# ADS_ExG.net
KiCad netlist of a schematic drawn in Altium Designer
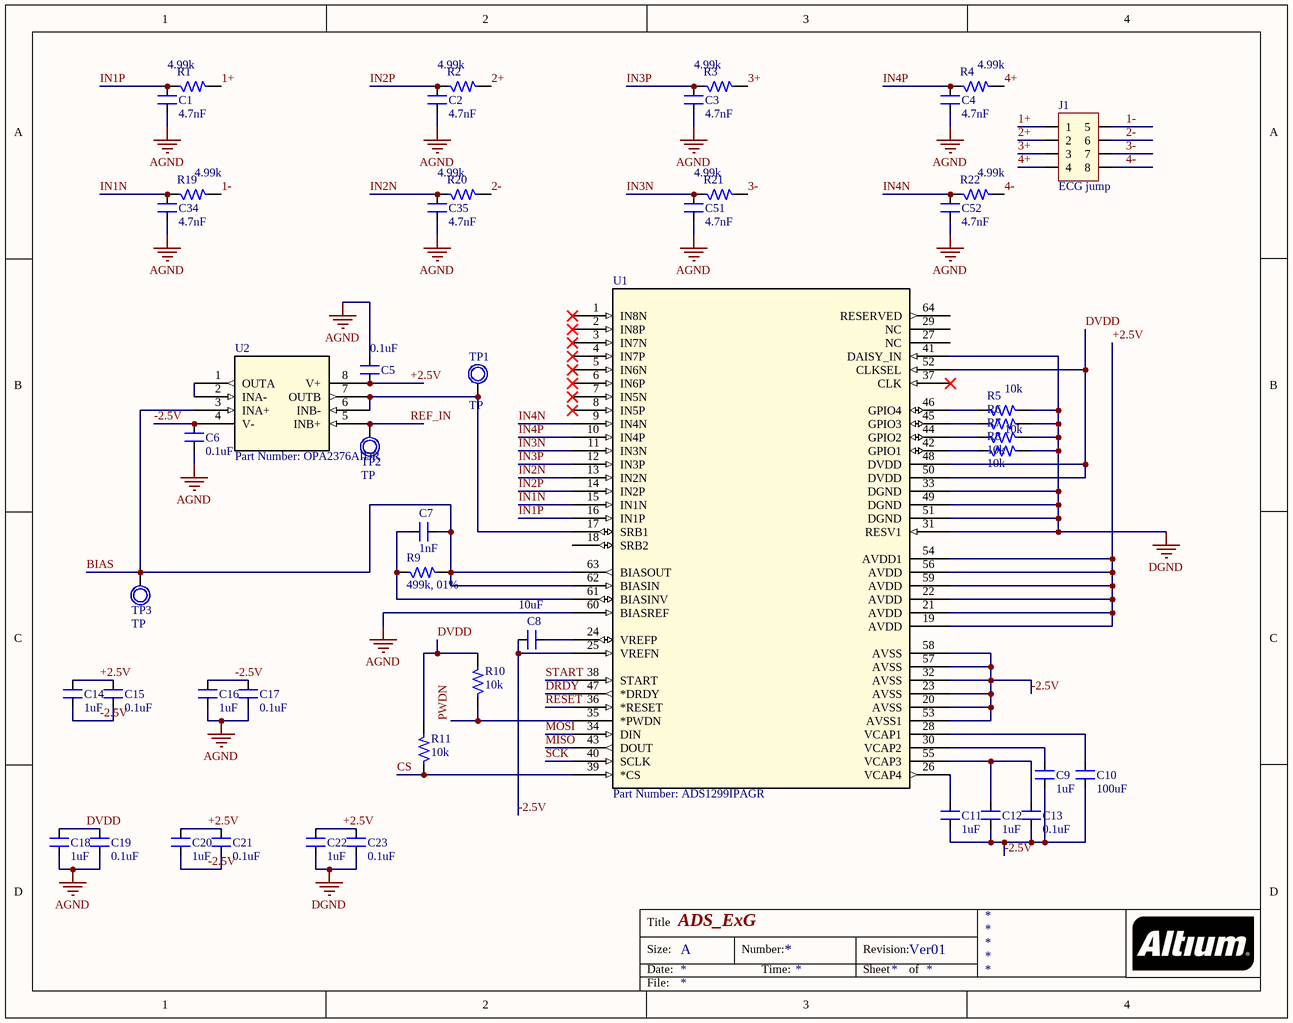
[diagram p0: ADS_ExG.SchDoc]

(export (version "E")
  (design (tool "Eeschema 10.0.6"))
  (components
    (comp (ref "C1")
      (value "4.7nF")
      (footprint "SM-0805")
      (description "Cap SMD")
      (libsource (lib "VioletofSun") (part "CM"))
    )
    (comp (ref "C2")
      (value "4.7nF")
      (footprint "SM-0805")
      (description "Cap SMD")
      (libsource (lib "VioletofSun") (part "CM"))
    )
    (comp (ref "C3")
      (value "4.7nF")
      (footprint "SM-0805")
      (description "Cap SMD")
      (libsource (lib "VioletofSun") (part "CM"))
    )
    (comp (ref "C4")
      (value "4.7nF")
      (footprint "SM-0805")
      (description "Cap SMD")
      (libsource (lib "VioletofSun") (part "CM"))
    )
    (comp (ref "C5")
      (value "0.1uF")
      (footprint "SM-0805")
      (description "Cap SMD")
      (libsource (lib "VioletofSun") (part "CM"))
    )
    (comp (ref "C6")
      (value "0.1uF")
      (footprint "SM-0805")
      (description "Cap SMD")
      (libsource (lib "VioletofSun") (part "CM"))
    )
    (comp (ref "C7")
      (value "1nF")
      (footprint "SM-0805")
      (description "Cap SMD")
      (libsource (lib "VioletofSun") (part "CM"))
    )
    (comp (ref "C8")
      (value "10uF")
      (footprint "SM-0805")
      (description "Cap SMD")
      (libsource (lib "VioletofSun") (part "CM"))
    )
    (comp (ref "C9")
      (value "1uF")
      (footprint "SM-0805")
      (description "Cap SMD")
      (libsource (lib "VioletofSun") (part "CM"))
    )
    (comp (ref "C10")
      (value "100uF")
      (footprint "SM-0805")
      (description "Cap SMD")
      (libsource (lib "VioletofSun") (part "CM"))
    )
    (comp (ref "C11")
      (value "1uF")
      (footprint "SM-0805")
      (description "Cap SMD")
      (libsource (lib "VioletofSun") (part "CM"))
    )
    (comp (ref "C12")
      (value "1uF")
      (footprint "SM-0805")
      (description "Cap SMD")
      (libsource (lib "VioletofSun") (part "CM"))
    )
    (comp (ref "C13")
      (value "0.1uF")
      (footprint "SM-0805")
      (description "Cap SMD")
      (libsource (lib "VioletofSun") (part "CM"))
    )
    (comp (ref "C14")
      (value "1uF")
      (footprint "SM-0805")
      (description "Cap SMD")
      (libsource (lib "VioletofSun") (part "CM"))
    )
    (comp (ref "C15")
      (value "0.1uF")
      (footprint "SM-0805")
      (description "Cap SMD")
      (libsource (lib "VioletofSun") (part "CM"))
    )
    (comp (ref "C16")
      (value "1uF")
      (footprint "SM-0805")
      (description "Cap SMD")
      (libsource (lib "VioletofSun") (part "CM"))
    )
    (comp (ref "C17")
      (value "0.1uF")
      (footprint "SM-0805")
      (description "Cap SMD")
      (libsource (lib "VioletofSun") (part "CM"))
    )
    (comp (ref "C18")
      (value "1uF")
      (footprint "SM-0805")
      (description "Cap SMD")
      (libsource (lib "VioletofSun") (part "CM"))
    )
    (comp (ref "C19")
      (value "0.1uF")
      (footprint "SM-0805")
      (description "Cap SMD")
      (libsource (lib "VioletofSun") (part "CM"))
    )
    (comp (ref "C20")
      (value "1uF")
      (footprint "SM-0805")
      (description "Cap SMD")
      (libsource (lib "VioletofSun") (part "CM"))
    )
    (comp (ref "C21")
      (value "0.1uF")
      (footprint "SM-0805")
      (description "Cap SMD")
      (libsource (lib "VioletofSun") (part "CM"))
    )
    (comp (ref "C22")
      (value "1uF")
      (footprint "SM-0805")
      (description "Cap SMD")
      (libsource (lib "VioletofSun") (part "CM"))
    )
    (comp (ref "C23")
      (value "0.1uF")
      (footprint "SM-0805")
      (description "Cap SMD")
      (libsource (lib "VioletofSun") (part "CM"))
    )
    (comp (ref "C34")
      (value "4.7nF")
      (footprint "SM-0805")
      (description "Cap SMD")
      (libsource (lib "VioletofSun") (part "CM"))
    )
    (comp (ref "C35")
      (value "4.7nF")
      (footprint "SM-0805")
      (description "Cap SMD")
      (libsource (lib "VioletofSun") (part "CM"))
    )
    (comp (ref "C51")
      (value "4.7nF")
      (footprint "SM-0805")
      (description "Cap SMD")
      (libsource (lib "VioletofSun") (part "CM"))
    )
    (comp (ref "C52")
      (value "4.7nF")
      (footprint "SM-0805")
      (description "Cap SMD")
      (libsource (lib "VioletofSun") (part "CM"))
    )
    (comp (ref "J1")
      (value "ECG jump")
      (footprint "JP4x2")
      (description "Connector 4x2")
      (libsource (lib "VioletofSun") (part "JP4x2"))
    )
    (comp (ref "R1")
      (value "4.99k")
      (footprint "SM-0805")
      (description "Resistor 1/4W")
      (libsource (lib "VioletofSun") (part "R"))
    )
    (comp (ref "R2")
      (value "4.99k")
      (footprint "SM-0805")
      (description "Resistor 1/4W")
      (libsource (lib "VioletofSun") (part "R"))
    )
    (comp (ref "R3")
      (value "4.99k")
      (footprint "SM-0805")
      (description "Resistor 1/4W")
      (libsource (lib "VioletofSun") (part "R"))
    )
    (comp (ref "R4")
      (value "4.99k")
      (footprint "SM-0805")
      (description "Resistor 1/4W")
      (libsource (lib "VioletofSun") (part "R"))
    )
    (comp (ref "R5")
      (value "10k")
      (footprint "SM-0805")
      (description "Resistor 1/4W")
      (libsource (lib "VioletofSun") (part "R"))
    )
    (comp (ref "R6")
      (value "10k")
      (footprint "SM-0805")
      (description "Resistor 1/4W")
      (libsource (lib "VioletofSun") (part "R"))
    )
    (comp (ref "R7")
      (value "10k")
      (footprint "SM-0805")
      (description "Resistor 1/4W")
      (libsource (lib "VioletofSun") (part "R"))
    )
    (comp (ref "R8")
      (value "10k")
      (footprint "SM-0805")
      (description "Resistor 1/4W")
      (libsource (lib "VioletofSun") (part "R"))
    )
    (comp (ref "R9")
      (value "499k, 01%")
      (footprint "SM-0805")
      (description "Resistor 1/4W")
      (libsource (lib "VioletofSun") (part "R"))
    )
    (comp (ref "R10")
      (value "10k")
      (footprint "SM-0805")
      (description "Resistor 1/4W")
      (libsource (lib "VioletofSun") (part "R"))
    )
    (comp (ref "R11")
      (value "10k")
      (footprint "SM-0805")
      (description "Resistor 1/4W")
      (libsource (lib "VioletofSun") (part "R"))
    )
    (comp (ref "R19")
      (value "4.99k")
      (footprint "SM-0805")
      (description "Resistor 1/4W")
      (libsource (lib "VioletofSun") (part "R"))
    )
    (comp (ref "R20")
      (value "4.99k")
      (footprint "SM-0805")
      (description "Resistor 1/4W")
      (libsource (lib "VioletofSun") (part "R"))
    )
    (comp (ref "R21")
      (value "4.99k")
      (footprint "SM-0805")
      (description "Resistor 1/4W")
      (libsource (lib "VioletofSun") (part "R"))
    )
    (comp (ref "R22")
      (value "4.99k")
      (footprint "SM-0805")
      (description "Resistor 1/4W")
      (libsource (lib "VioletofSun") (part "R"))
    )
    (comp (ref "TP1")
      (value "TP")
      (footprint "VioletofSun:TP1")
      (description "Test Point")
      (libsource (lib "") (part "TP1_1"))
    )
    (comp (ref "TP2")
      (value "TP")
      (footprint "VioletofSun:TP1")
      (description "Test Point")
      (libsource (lib "VioletofSun") (part "TP1"))
    )
    (comp (ref "TP3")
      (value "TP")
      (footprint "VioletofSun:TP1")
      (description "Test Point")
      (libsource (lib "VioletofSun") (part "TP1"))
    )
    (comp (ref "U1")
      (value "Part Number: ADS1299IPAGR")
      (footprint "PAG64")
      (description "No Description Available")
      (fields
        (field (name "MANUFACTURER_PART_NUMBER") "ADS1299IPAGR")
        (field (name "COPYRIGHT") "Copyright (C) 2018 Accelerated Designs. All rights reserved")
      )
      (libsource (lib "ADS1299IPAGR") (part "ADS1299IPAGR"))
    )
    (comp (ref "U2")
      (value "Part Number: OPA2376AIDR")
      (footprint "D8")
      (description "No Description Available")
      (fields
        (field (name "MANUFACTURER_PART_NUMBER") "OPA2376AIDR")
        (field (name "COPYRIGHT") "Copyright (C) 2018 Accelerated Designs. All rights reserved")
      )
      (libsource (lib "2019-06-26_00-32-27") (part "OPA2376AIDR"))
    )
  )
  (nets
    (net (code "1") (name "/+2.5V") (class "Default")
      (node (ref "C14") (pin "2") (pinfunction "2_2") (pintype "passive"))
      (node (ref "C15") (pin "2") (pinfunction "2_2") (pintype "passive"))
      (node (ref "C20") (pin "2") (pinfunction "2_2") (pintype "passive"))
      (node (ref "C21") (pin "2") (pinfunction "2_2") (pintype "passive"))
      (node (ref "C22") (pin "2") (pinfunction "2_2") (pintype "passive"))
      (node (ref "C23") (pin "2") (pinfunction "2_2") (pintype "passive"))
      (node (ref "C5") (pin "1") (pinfunction "1_1") (pintype "passive"))
      (node (ref "U1") (pin "19") (pinfunction "AVDD_19") (pintype "power_in"))
      (node (ref "U1") (pin "21") (pinfunction "AVDD_21") (pintype "power_in"))
      (node (ref "U1") (pin "22") (pinfunction "AVDD_22") (pintype "power_in"))
      (node (ref "U1") (pin "54") (pinfunction "AVDD1_54") (pintype "power_in"))
      (node (ref "U1") (pin "56") (pinfunction "AVDD_56") (pintype "power_in"))
      (node (ref "U1") (pin "59") (pinfunction "AVDD_59") (pintype "power_in"))
      (node (ref "U2") (pin "8") (pinfunction "V+_8") (pintype "power_in"))
    )
    (net (code "2") (name "/-2.5V") (class "Default")
      (node (ref "C10") (pin "2") (pinfunction "2_2") (pintype "passive"))
      (node (ref "C11") (pin "1") (pinfunction "1_1") (pintype "passive"))
      (node (ref "C12") (pin "1") (pinfunction "1_1") (pintype "passive"))
      (node (ref "C13") (pin "1") (pinfunction "1_1") (pintype "passive"))
      (node (ref "C14") (pin "1") (pinfunction "1_1") (pintype "passive"))
      (node (ref "C15") (pin "1") (pinfunction "1_1") (pintype "passive"))
      (node (ref "C16") (pin "2") (pinfunction "2_2") (pintype "passive"))
      (node (ref "C17") (pin "2") (pinfunction "2_2") (pintype "passive"))
      (node (ref "C20") (pin "1") (pinfunction "1_1") (pintype "passive"))
      (node (ref "C21") (pin "1") (pinfunction "1_1") (pintype "passive"))
      (node (ref "C6") (pin "2") (pinfunction "2_2") (pintype "passive"))
      (node (ref "C8") (pin "2") (pinfunction "2_2") (pintype "passive"))
      (node (ref "C9") (pin "1") (pinfunction "1_1") (pintype "passive"))
      (node (ref "U1") (pin "20") (pinfunction "AVSS_20") (pintype "power_in"))
      (node (ref "U1") (pin "23") (pinfunction "AVSS_23") (pintype "power_in"))
      (node (ref "U1") (pin "25") (pinfunction "VREFN_25") (pintype "input"))
      (node (ref "U1") (pin "32") (pinfunction "AVSS_32") (pintype "power_in"))
      (node (ref "U1") (pin "53") (pinfunction "AVSS1_53") (pintype "power_in"))
      (node (ref "U1") (pin "57") (pinfunction "AVSS_57") (pintype "power_in"))
      (node (ref "U1") (pin "58") (pinfunction "AVSS_58") (pintype "power_in"))
      (node (ref "U2") (pin "4") (pinfunction "V-_4") (pintype "power_in"))
    )
    (net (code "3") (name "/1+") (class "Default")
      (node (ref "J1") (pin "1") (pinfunction "1_1") (pintype "passive"))
      (node (ref "R1") (pin "2") (pinfunction "2_2") (pintype "passive"))
    )
    (net (code "4") (name "/1-") (class "Default")
      (node (ref "J1") (pin "5") (pinfunction "5_5") (pintype "passive"))
      (node (ref "R19") (pin "2") (pinfunction "2_2") (pintype "passive"))
    )
    (net (code "5") (name "/2+") (class "Default")
      (node (ref "J1") (pin "2") (pinfunction "2_2") (pintype "passive"))
      (node (ref "R2") (pin "2") (pinfunction "2_2") (pintype "passive"))
    )
    (net (code "6") (name "/2-") (class "Default")
      (node (ref "J1") (pin "6") (pinfunction "6_6") (pintype "passive"))
      (node (ref "R20") (pin "2") (pinfunction "2_2") (pintype "passive"))
    )
    (net (code "7") (name "/3+") (class "Default")
      (node (ref "J1") (pin "3") (pinfunction "3_3") (pintype "passive"))
      (node (ref "R3") (pin "2") (pinfunction "2_2") (pintype "passive"))
    )
    (net (code "8") (name "/3-") (class "Default")
      (node (ref "J1") (pin "7") (pinfunction "7_7") (pintype "passive"))
      (node (ref "R21") (pin "2") (pinfunction "2_2") (pintype "passive"))
    )
    (net (code "9") (name "/4+") (class "Default")
      (node (ref "J1") (pin "4") (pinfunction "4_4") (pintype "passive"))
      (node (ref "R4") (pin "2") (pinfunction "2_2") (pintype "passive"))
    )
    (net (code "10") (name "/4-") (class "Default")
      (node (ref "J1") (pin "8") (pinfunction "8_8") (pintype "passive"))
      (node (ref "R22") (pin "2") (pinfunction "2_2") (pintype "passive"))
    )
    (net (code "11") (name "/BIAS") (class "Default")
      (node (ref "C7") (pin "2") (pinfunction "2_2") (pintype "passive"))
      (node (ref "R9") (pin "2") (pinfunction "2_2") (pintype "passive"))
      (node (ref "TP3") (pin "1") (pinfunction "1_1") (pintype "passive"))
      (node (ref "U1") (pin "62") (pinfunction "BIASIN_62") (pintype "input"))
      (node (ref "U1") (pin "63") (pinfunction "BIASOUT_63") (pintype "output"))
      (node (ref "U2") (pin "3") (pinfunction "INA+_3") (pintype "input"))
    )
    (net (code "12") (name "/CS") (class "Default")
      (node (ref "R11") (pin "1") (pinfunction "1_1") (pintype "passive"))
      (node (ref "U1") (pin "39") (pinfunction "*CS_39") (pintype "input"))
    )
    (net (code "13") (name "/DRDY") (class "Default")
      (node (ref "U1") (pin "47") (pinfunction "*DRDY_47") (pintype "output"))
    )
    (net (code "14") (name "/DVDD") (class "Default")
      (node (ref "C18") (pin "2") (pinfunction "2_2") (pintype "passive"))
      (node (ref "C19") (pin "2") (pinfunction "2_2") (pintype "passive"))
      (node (ref "R10") (pin "2") (pinfunction "2_2") (pintype "passive"))
      (node (ref "R11") (pin "2") (pinfunction "2_2") (pintype "passive"))
      (node (ref "U1") (pin "48") (pinfunction "DVDD_48") (pintype "power_in"))
      (node (ref "U1") (pin "50") (pinfunction "DVDD_50") (pintype "power_in"))
      (node (ref "U1") (pin "52") (pinfunction "CLKSEL_52") (pintype "input"))
    )
    (net (code "15") (name "/IN1N") (class "Default")
      (node (ref "C34") (pin "2") (pinfunction "2_2") (pintype "passive"))
      (node (ref "R19") (pin "1") (pinfunction "1_1") (pintype "passive"))
      (node (ref "U1") (pin "15") (pinfunction "IN1N_15") (pintype "input"))
    )
    (net (code "16") (name "/IN1P") (class "Default")
      (node (ref "C1") (pin "2") (pinfunction "2_2") (pintype "passive"))
      (node (ref "R1") (pin "1") (pinfunction "1_1") (pintype "passive"))
      (node (ref "U1") (pin "16") (pinfunction "IN1P_16") (pintype "input"))
    )
    (net (code "17") (name "/IN2N") (class "Default")
      (node (ref "C35") (pin "2") (pinfunction "2_2") (pintype "passive"))
      (node (ref "R20") (pin "1") (pinfunction "1_1") (pintype "passive"))
      (node (ref "U1") (pin "13") (pinfunction "IN2N_13") (pintype "input"))
    )
    (net (code "18") (name "/IN2P") (class "Default")
      (node (ref "C2") (pin "2") (pinfunction "2_2") (pintype "passive"))
      (node (ref "R2") (pin "1") (pinfunction "1_1") (pintype "passive"))
      (node (ref "U1") (pin "14") (pinfunction "IN2P_14") (pintype "input"))
    )
    (net (code "19") (name "/IN3N") (class "Default")
      (node (ref "C51") (pin "2") (pinfunction "2_2") (pintype "passive"))
      (node (ref "R21") (pin "1") (pinfunction "1_1") (pintype "passive"))
      (node (ref "U1") (pin "11") (pinfunction "IN3N_11") (pintype "input"))
    )
    (net (code "20") (name "/IN3P") (class "Default")
      (node (ref "C3") (pin "2") (pinfunction "2_2") (pintype "passive"))
      (node (ref "R3") (pin "1") (pinfunction "1_1") (pintype "passive"))
      (node (ref "U1") (pin "12") (pinfunction "IN3P_12") (pintype "input"))
    )
    (net (code "21") (name "/IN4N") (class "Default")
      (node (ref "C52") (pin "2") (pinfunction "2_2") (pintype "passive"))
      (node (ref "R22") (pin "1") (pinfunction "1_1") (pintype "passive"))
      (node (ref "U1") (pin "9") (pinfunction "IN4N_9") (pintype "input"))
    )
    (net (code "22") (name "/IN4P") (class "Default")
      (node (ref "C4") (pin "2") (pinfunction "2_2") (pintype "passive"))
      (node (ref "R4") (pin "1") (pinfunction "1_1") (pintype "passive"))
      (node (ref "U1") (pin "10") (pinfunction "IN4P_10") (pintype "input"))
    )
    (net (code "23") (name "/MISO") (class "Default")
      (node (ref "U1") (pin "43") (pinfunction "DOUT_43") (pintype "output"))
    )
    (net (code "24") (name "/MOSI") (class "Default")
      (node (ref "U1") (pin "34") (pinfunction "DIN_34") (pintype "input"))
    )
    (net (code "25") (name "/PWDN") (class "Default")
      (node (ref "R10") (pin "1") (pinfunction "1_1") (pintype "passive"))
      (node (ref "U1") (pin "35") (pinfunction "*PWDN_35") (pintype "power_in"))
    )
    (net (code "26") (name "/REF_IN") (class "Default")
      (node (ref "TP2") (pin "1") (pinfunction "1_1") (pintype "passive"))
      (node (ref "U2") (pin "5") (pinfunction "INB+_5") (pintype "input"))
    )
    (net (code "27") (name "/RESET") (class "Default")
      (node (ref "U1") (pin "36") (pinfunction "*RESET_36") (pintype "input"))
    )
    (net (code "28") (name "/SCK") (class "Default")
      (node (ref "U1") (pin "40") (pinfunction "SCLK_40") (pintype "input"))
    )
    (net (code "29") (name "/START") (class "Default")
      (node (ref "U1") (pin "38") (pinfunction "START_38") (pintype "input"))
    )
    (net (code "30") (name "AGND") (class "Default")
      (node (ref "C1") (pin "1") (pinfunction "1_1") (pintype "passive"))
      (node (ref "C16") (pin "1") (pinfunction "1_1") (pintype "passive"))
      (node (ref "C17") (pin "1") (pinfunction "1_1") (pintype "passive"))
      (node (ref "C18") (pin "1") (pinfunction "1_1") (pintype "passive"))
      (node (ref "C19") (pin "1") (pinfunction "1_1") (pintype "passive"))
      (node (ref "C2") (pin "1") (pinfunction "1_1") (pintype "passive"))
      (node (ref "C3") (pin "1") (pinfunction "1_1") (pintype "passive"))
      (node (ref "C34") (pin "1") (pinfunction "1_1") (pintype "passive"))
      (node (ref "C35") (pin "1") (pinfunction "1_1") (pintype "passive"))
      (node (ref "C4") (pin "1") (pinfunction "1_1") (pintype "passive"))
      (node (ref "C5") (pin "2") (pinfunction "2_2") (pintype "passive"))
      (node (ref "C51") (pin "1") (pinfunction "1_1") (pintype "passive"))
      (node (ref "C52") (pin "1") (pinfunction "1_1") (pintype "passive"))
      (node (ref "C6") (pin "1") (pinfunction "1_1") (pintype "passive"))
      (node (ref "U1") (pin "60") (pinfunction "BIASREF_60") (pintype "input"))
    )
    (net (code "31") (name "DGND") (class "Default")
      (node (ref "C22") (pin "1") (pinfunction "1_1") (pintype "passive"))
      (node (ref "C23") (pin "1") (pinfunction "1_1") (pintype "passive"))
      (node (ref "R5") (pin "2") (pinfunction "2_2") (pintype "passive"))
      (node (ref "R6") (pin "2") (pinfunction "2_2") (pintype "passive"))
      (node (ref "R7") (pin "2") (pinfunction "2_2") (pintype "passive"))
      (node (ref "R8") (pin "2") (pinfunction "2_2") (pintype "passive"))
      (node (ref "U1") (pin "31") (pinfunction "RESV1_31") (pintype "input"))
      (node (ref "U1") (pin "33") (pinfunction "DGND_33") (pintype "power_in"))
      (node (ref "U1") (pin "41") (pinfunction "DAISY_IN_41") (pintype "input"))
      (node (ref "U1") (pin "49") (pinfunction "DGND_49") (pintype "power_in"))
      (node (ref "U1") (pin "51") (pinfunction "DGND_51") (pintype "power_in"))
    )
    (net (code "32") (name "Net-(U1-BIASINV)") (class "Default")
      (node (ref "C7") (pin "1") (pinfunction "1_1") (pintype "passive"))
      (node (ref "R9") (pin "1") (pinfunction "1_1") (pintype "passive"))
      (node (ref "U1") (pin "61") (pinfunction "BIASINV_61") (pintype "bidirectional"))
    )
    (net (code "33") (name "Net-(U1-GPIO1)") (class "Default")
      (node (ref "R8") (pin "1") (pinfunction "1_1") (pintype "passive"))
      (node (ref "U1") (pin "42") (pinfunction "GPIO1_42") (pintype "bidirectional"))
    )
    (net (code "34") (name "Net-(U1-GPIO2)") (class "Default")
      (node (ref "R7") (pin "1") (pinfunction "1_1") (pintype "passive"))
      (node (ref "U1") (pin "44") (pinfunction "GPIO2_44") (pintype "bidirectional"))
    )
    (net (code "35") (name "Net-(U1-GPIO3)") (class "Default")
      (node (ref "R6") (pin "1") (pinfunction "1_1") (pintype "passive"))
      (node (ref "U1") (pin "45") (pinfunction "GPIO3_45") (pintype "bidirectional"))
    )
    (net (code "36") (name "Net-(U1-GPIO4)") (class "Default")
      (node (ref "R5") (pin "1") (pinfunction "1_1") (pintype "passive"))
      (node (ref "U1") (pin "46") (pinfunction "GPIO4_46") (pintype "bidirectional"))
    )
    (net (code "37") (name "Net-(U1-SRB1)") (class "Default")
      (node (ref "TP1") (pin "1") (pinfunction "1_1") (pintype "passive"))
      (node (ref "U1") (pin "17") (pinfunction "SRB1_17") (pintype "bidirectional"))
      (node (ref "U2") (pin "6") (pinfunction "INB-_6") (pintype "input"))
      (node (ref "U2") (pin "7") (pinfunction "OUTB_7") (pintype "output"))
    )
    (net (code "38") (name "Net-(U1-VCAP1)") (class "Default")
      (node (ref "C10") (pin "1") (pinfunction "1_1") (pintype "passive"))
      (node (ref "U1") (pin "28") (pinfunction "VCAP1_28") (pintype "passive"))
    )
    (net (code "39") (name "Net-(U1-VCAP2)") (class "Default")
      (node (ref "C9") (pin "2") (pinfunction "2_2") (pintype "passive"))
      (node (ref "U1") (pin "30") (pinfunction "VCAP2_30") (pintype "passive"))
    )
    (net (code "40") (name "Net-(U1-VCAP3)") (class "Default")
      (node (ref "C12") (pin "2") (pinfunction "2_2") (pintype "passive"))
      (node (ref "C13") (pin "2") (pinfunction "2_2") (pintype "passive"))
      (node (ref "U1") (pin "55") (pinfunction "VCAP3_55") (pintype "passive"))
    )
    (net (code "41") (name "Net-(U1-VCAP4)") (class "Default")
      (node (ref "C11") (pin "2") (pinfunction "2_2") (pintype "passive"))
      (node (ref "U1") (pin "26") (pinfunction "VCAP4_26") (pintype "output"))
    )
    (net (code "42") (name "Net-(U1-VREFP)") (class "Default")
      (node (ref "C8") (pin "1") (pinfunction "1_1") (pintype "passive"))
      (node (ref "U1") (pin "24") (pinfunction "VREFP_24") (pintype "bidirectional"))
    )
    (net (code "43") (name "Net-(U2-INA-)") (class "Default")
      (node (ref "U2") (pin "1") (pinfunction "OUTA_1") (pintype "output"))
      (node (ref "U2") (pin "2") (pinfunction "INA-_2") (pintype "input"))
    )
    (net (code "44") (name "unconnected-(U1-CLK-Pad37)") (class "Default")
      (node (ref "U1") (pin "37") (pinfunction "CLK_37") (pintype "input+no_connect"))
    )
    (net (code "45") (name "unconnected-(U1-IN5N-Pad7)") (class "Default")
      (node (ref "U1") (pin "7") (pinfunction "IN5N_7") (pintype "input+no_connect"))
    )
    (net (code "46") (name "unconnected-(U1-IN5P-Pad8)") (class "Default")
      (node (ref "U1") (pin "8") (pinfunction "IN5P_8") (pintype "input+no_connect"))
    )
    (net (code "47") (name "unconnected-(U1-IN6N-Pad5)") (class "Default")
      (node (ref "U1") (pin "5") (pinfunction "IN6N_5") (pintype "input+no_connect"))
    )
    (net (code "48") (name "unconnected-(U1-IN6P-Pad6)") (class "Default")
      (node (ref "U1") (pin "6") (pinfunction "IN6P_6") (pintype "input+no_connect"))
    )
    (net (code "49") (name "unconnected-(U1-IN7N-Pad3)") (class "Default")
      (node (ref "U1") (pin "3") (pinfunction "IN7N_3") (pintype "input+no_connect"))
    )
    (net (code "50") (name "unconnected-(U1-IN7P-Pad4)") (class "Default")
      (node (ref "U1") (pin "4") (pinfunction "IN7P_4") (pintype "input+no_connect"))
    )
    (net (code "51") (name "unconnected-(U1-IN8N-Pad1)") (class "Default")
      (node (ref "U1") (pin "1") (pinfunction "IN8N_1") (pintype "input+no_connect"))
    )
    (net (code "52") (name "unconnected-(U1-IN8P-Pad2)") (class "Default")
      (node (ref "U1") (pin "2") (pinfunction "IN8P_2") (pintype "input+no_connect"))
    )
    (net (code "53") (name "unconnected-(U1-NC-Pad27)") (class "Default")
      (node (ref "U1") (pin "27") (pinfunction "NC_27") (pintype "passive"))
    )
    (net (code "54") (name "unconnected-(U1-NC-Pad29)") (class "Default")
      (node (ref "U1") (pin "29") (pinfunction "NC_29") (pintype "passive"))
    )
    (net (code "55") (name "unconnected-(U1-RESERVED-Pad64)") (class "Default")
      (node (ref "U1") (pin "64") (pinfunction "RESERVED_64") (pintype "output"))
    )
    (net (code "56") (name "unconnected-(U1-SRB2-Pad18)") (class "Default")
      (node (ref "U1") (pin "18") (pinfunction "SRB2_18") (pintype "bidirectional"))
    )
  )
)
